# Sawtooth_Generator.net
KiCad netlist of a schematic drawn in Altium Designer
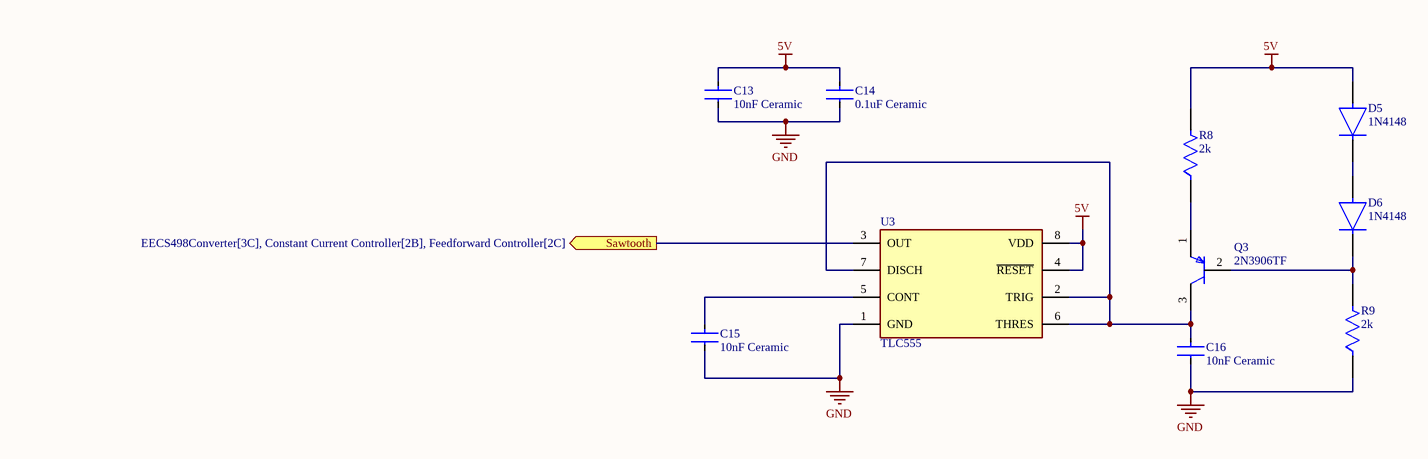
[diagram p0: Sawtooth Generator.SchDoc]

(export (version "E")
  (design (tool "Eeschema 10.0.6"))
  (components
    (comp (ref "C13")
      (value "10nF Ceramic")
      (footprint "FP-K15H5-MFG")
      (description "CAP CER 10nF 50V X7R RADIAL")
      (fields (field (name "TOLERANCE") "10%") (field (name "VOLTAGE") "50V"))
      (libsource (lib "EECS498Converter") (part "10nF Capacitor"))
    )
    (comp (ref "C14")
      (value "0.1uF Ceramic")
      (footprint "FP-K15H5-MFG")
      (description "CAP CER 0.1UF 50V X7R RADIAL")
      (fields (field (name "TOLERANCE") "10%") (field (name "VOLTAGE") "50V"))
      (libsource (lib "EECS498Converter") (part "0.1uF Capacitor"))
    )
    (comp (ref "C15")
      (value "10nF Ceramic")
      (footprint "FP-K15H5-MFG")
      (description "CAP CER 10nF 50V X7R RADIAL")
      (fields (field (name "TOLERANCE") "10%") (field (name "VOLTAGE") "50V"))
      (libsource (lib "EECS498Converter") (part "10nF Capacitor"))
    )
    (comp (ref "C16")
      (value "10nF Ceramic")
      (footprint "FP-K15H5-MFG")
      (description "CAP CER 10nF 50V X7R RADIAL")
      (fields (field (name "TOLERANCE") "10%") (field (name "VOLTAGE") "50V"))
      (libsource (lib "EECS498Converter") (part "10nF Capacitor"))
    )
    (comp (ref "D5")
      (value "1N4148")
      (footprint "FP-1N4148-MFG")
      (description "DIODE GEN PURP 100V 200MA DO35")
      (fields (field (name "VOLTAGE") "100V"))
      (libsource (lib "EECS498Converter") (part "1N4148"))
    )
    (comp (ref "D6")
      (value "1N4148")
      (footprint "FP-1N4148-MFG")
      (description "DIODE GEN PURP 100V 200MA DO35")
      (fields (field (name "VOLTAGE") "100V"))
      (libsource (lib "EECS498Converter") (part "1N4148"))
    )
    (comp (ref "Q3")
      (value "2N3906TF")
      (footprint "2N3906TF")
      (description "2N3906TF Small Signal Bipolar Transistor, 0.2A I(C), 40V V(BR)CEO, 1-Element, PNP, Silicon, TO-92")
      (libsource (lib "EECS498Converter") (part "2N3906TF"))
    )
    (comp (ref "R8")
      (value "2k")
      (footprint "FP-RLR07-MFG")
      (description "Resistor, ± 1%, 250 mW, Axial Leaded, Metal Film, Military Reliability")
      (fields (field (name "TOLERANCE") "1%"))
      (libsource (lib "EECS498Converter") (part "Resistor"))
    )
    (comp (ref "R9")
      (value "2k")
      (footprint "FP-RLR07-MFG")
      (description "Resistor, ± 1%, 250 mW, Axial Leaded, Metal Film, Military Reliability")
      (fields (field (name "TOLERANCE") "1%"))
      (libsource (lib "EECS498Converter") (part "Resistor"))
    )
    (comp (ref "U3")
      (value "TLC555")
      (footprint "DIP8")
      (description "IC OSC SGL TIMER 2.1MHZ 8-SOIC")
      (libsource (lib "EECS498Converter") (part "TLC555"))
    )
  )
  (nets
    (net (code "1") (name "/Sawtooth") (class "Default")
      (node (ref "U3") (pin "3") (pinfunction "OUT_3") (pintype "passive"))
    )
    (net (code "2") (name "5V") (class "Default")
      (node (ref "C13") (pin "1") (pinfunction "1_1") (pintype "passive"))
      (node (ref "C14") (pin "1") (pinfunction "1_1") (pintype "passive"))
      (node (ref "D5") (pin "2") (pinfunction "A_2") (pintype "passive"))
      (node (ref "R8") (pin "2") (pinfunction "2_2") (pintype "passive"))
      (node (ref "U3") (pin "4") (pinfunction "~{RESET}_4") (pintype "passive"))
      (node (ref "U3") (pin "8") (pinfunction "VDD_8") (pintype "power_in"))
    )
    (net (code "3") (name "GND") (class "Default")
      (node (ref "C13") (pin "2") (pinfunction "2_2") (pintype "passive"))
      (node (ref "C14") (pin "2") (pinfunction "2_2") (pintype "passive"))
      (node (ref "C15") (pin "2") (pinfunction "2_2") (pintype "passive"))
      (node (ref "C16") (pin "2") (pinfunction "2_2") (pintype "passive"))
      (node (ref "R9") (pin "1") (pinfunction "1_1") (pintype "passive"))
      (node (ref "U3") (pin "1") (pinfunction "GND_1") (pintype "power_in"))
    )
    (net (code "4") (name "Net-(D5-C)") (class "Default")
      (node (ref "D5") (pin "1") (pinfunction "C_1") (pintype "passive"))
      (node (ref "D6") (pin "2") (pinfunction "A_2") (pintype "passive"))
    )
    (net (code "5") (name "Net-(D6-C)") (class "Default")
      (node (ref "D6") (pin "1") (pinfunction "C_1") (pintype "passive"))
      (node (ref "Q3") (pin "2") (pinfunction "B_2") (pintype "passive"))
      (node (ref "R9") (pin "2") (pinfunction "2_2") (pintype "passive"))
    )
    (net (code "6") (name "Net-(Q3-C)") (class "Default")
      (node (ref "C16") (pin "1") (pinfunction "1_1") (pintype "passive"))
      (node (ref "Q3") (pin "3") (pinfunction "C_3") (pintype "passive"))
      (node (ref "U3") (pin "2") (pinfunction "TRIG_2") (pintype "passive"))
      (node (ref "U3") (pin "6") (pinfunction "THRES_6") (pintype "passive"))
      (node (ref "U3") (pin "7") (pinfunction "DISCH_7") (pintype "passive"))
    )
    (net (code "7") (name "Net-(Q3-E)") (class "Default")
      (node (ref "Q3") (pin "1") (pinfunction "E_1") (pintype "passive"))
      (node (ref "R8") (pin "1") (pinfunction "1_1") (pintype "passive"))
    )
    (net (code "8") (name "Net-(U3-CONT)") (class "Default")
      (node (ref "C15") (pin "1") (pinfunction "1_1") (pintype "passive"))
      (node (ref "U3") (pin "5") (pinfunction "CONT_5") (pintype "passive"))
    )
  )
)
